# STM32F405.net
KiCad netlist of a schematic drawn in Altium Designer
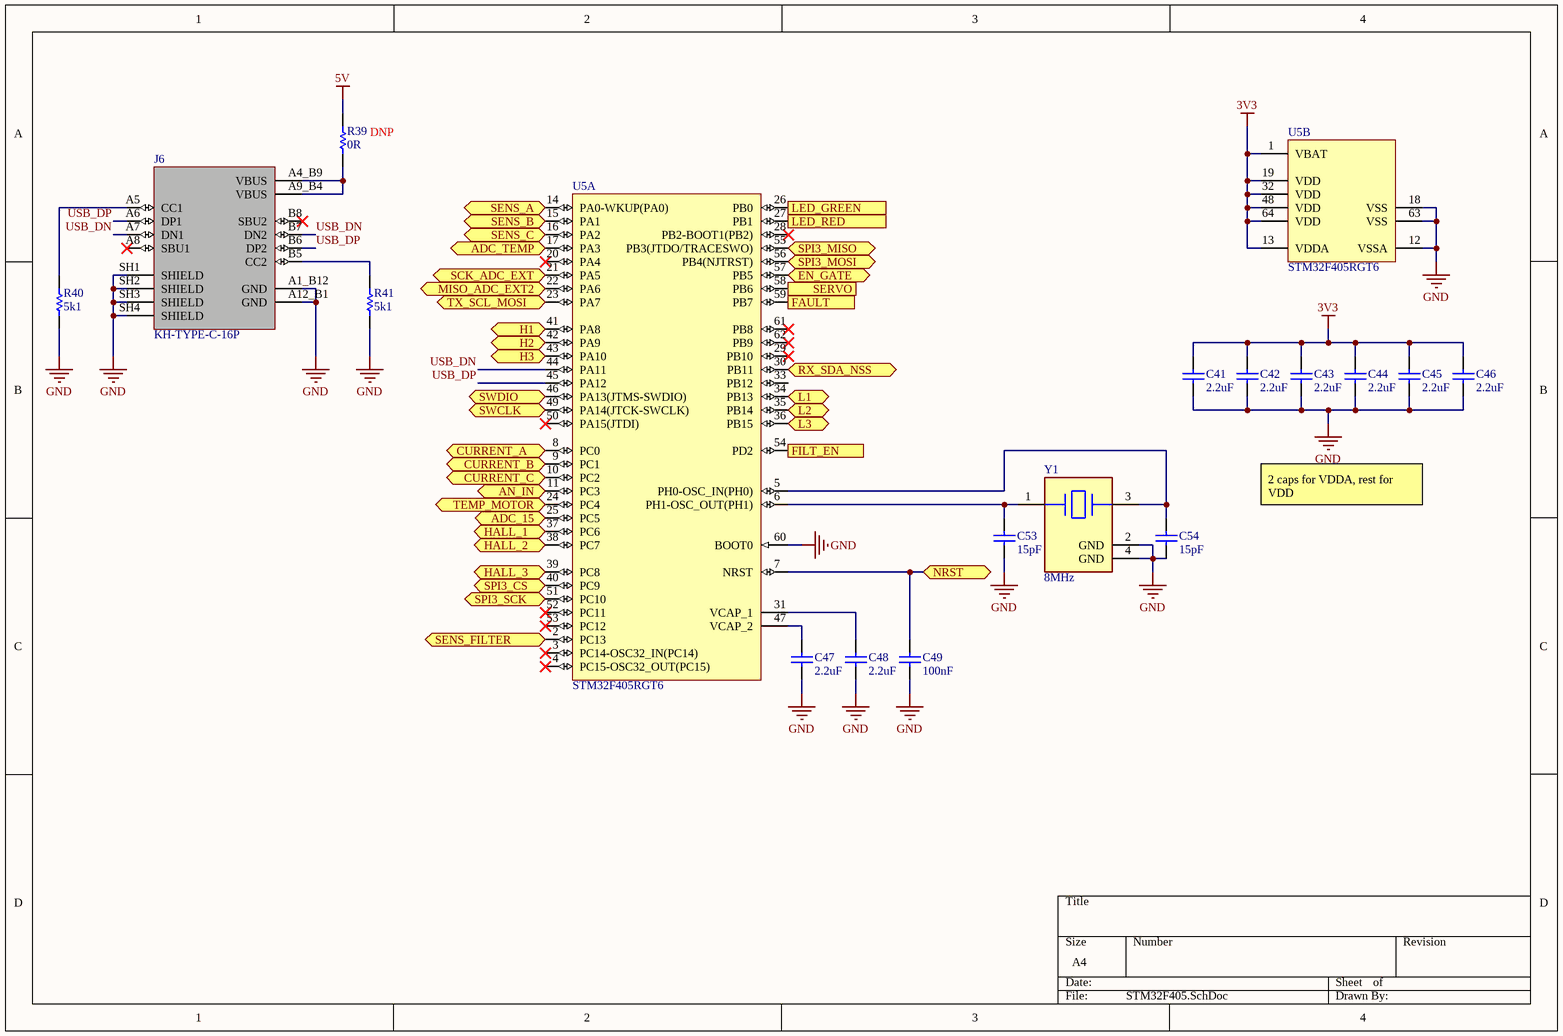
[diagram p0: STM32F405.SchDoc]

(export (version "E")
  (design (tool "Eeschema 10.0.6"))
  (components
    (comp (ref "C41")
      (value "2.2uF")
      (footprint "Wurth 0603 capacitor")
      (fields (field (name "Comment") "Generic Capacitor 2.2uF 0603"))
      (libsource (lib "Passives") (part "Generic Capacitor 2.2uF 0603"))
    )
    (comp (ref "C42")
      (value "2.2uF")
      (footprint "Wurth 0603 capacitor")
      (fields (field (name "Comment") "Generic Capacitor 2.2uF 0603"))
      (libsource (lib "Passives") (part "Generic Capacitor 2.2uF 0603"))
    )
    (comp (ref "C43")
      (value "2.2uF")
      (footprint "Wurth 0603 capacitor")
      (fields (field (name "Comment") "Generic Capacitor 2.2uF 0603"))
      (libsource (lib "Passives") (part "Generic Capacitor 2.2uF 0603"))
    )
    (comp (ref "C44")
      (value "2.2uF")
      (footprint "Wurth 0603 capacitor")
      (fields (field (name "Comment") "Generic Capacitor 2.2uF 0603"))
      (libsource (lib "Passives") (part "Generic Capacitor 2.2uF 0603"))
    )
    (comp (ref "C45")
      (value "2.2uF")
      (footprint "Wurth 0603 capacitor")
      (fields (field (name "Comment") "Generic Capacitor 2.2uF 0603"))
      (libsource (lib "Passives") (part "Generic Capacitor 2.2uF 0603"))
    )
    (comp (ref "C46")
      (value "2.2uF")
      (footprint "Wurth 0603 capacitor")
      (fields (field (name "Comment") "Generic Capacitor 2.2uF 0603"))
      (libsource (lib "Passives") (part "Generic Capacitor 2.2uF 0603"))
    )
    (comp (ref "C47")
      (value "2.2uF")
      (footprint "Wurth 0603 capacitor")
      (fields (field (name "Comment") "Generic Capacitor 2.2uF 0603"))
      (libsource (lib "Passives") (part "Generic Capacitor 2.2uF 0603"))
    )
    (comp (ref "C48")
      (value "2.2uF")
      (footprint "Wurth 0603 capacitor")
      (fields (field (name "Comment") "Generic Capacitor 2.2uF 0603"))
      (libsource (lib "Passives") (part "Generic Capacitor 2.2uF 0603"))
    )
    (comp (ref "C49")
      (value "100nF")
      (footprint "Wurth 0603 capacitor")
      (fields (field (name "Comment") "Generic Capacitor 100nF 0603"))
      (libsource (lib "Passives") (part "Generic Capacitor 100nF 0603"))
    )
    (comp (ref "C53")
      (value "15pF")
      (footprint "Wurth 0603 capacitor")
      (fields (field (name "Comment") "Generic Capacitor 15pF 0603"))
      (libsource (lib "Passives") (part "Generic Capacitor 15pF 0603"))
    )
    (comp (ref "C54")
      (value "15pF")
      (footprint "Wurth 0603 capacitor")
      (fields (field (name "Comment") "Generic Capacitor 15pF 0603"))
      (libsource (lib "Passives") (part "Generic Capacitor 15pF 0603"))
    )
    (comp (ref "J6")
      (value "KH-TYPE-C-16P")
      (footprint "KINGHELM_KH-TYPE-C-16P")
      (fields (field (name "MF") "kinghelm"))
      (libsource (lib "Connectors") (part "KH-TYPE-C-16P"))
    )
    (comp (ref "R39")
      (value "0R")
      (footprint "Wurth 0603 Resistor")
      (fields (field (name "Comment") "Generic Resistor 0R 0603"))
      (libsource (lib "Passives") (part "Generic Resistor 0R 0603"))
    )
    (comp (ref "R40")
      (value "5k1")
      (footprint "0805 Resistor")
      (fields (field (name "Comment") "Generic Resistor 5k1 0805"))
      (libsource (lib "Passives") (part "Generic Resistor 5k1 0805"))
    )
    (comp (ref "R41")
      (value "5k1")
      (footprint "0805 Resistor")
      (fields (field (name "Comment") "Generic Resistor 5k1 0805"))
      (libsource (lib "Passives") (part "Generic Resistor 5k1 0805"))
    )
    (comp (ref "U5")
      (value "STM32F405RGT6")
      (footprint "STM-LQFP64_M")
      (fields (field (name "MANUFACTURER") "STMicroelectronics"))
      (libsource (lib "Altium Content Vault") (part "MC-ARM-STM32F4X5-SQ64"))
    )
    (comp (ref "Y1")
      (value "8MHz")
      (footprint "huaxindianzi 8MHz Crystal")
      (fields (field (name "Comment") "CF4008M00012001"))
      (libsource (lib "Crystals") (part "8MHz huaxindianzi Crystal"))
    )
  )
  (nets
    (net (code "1") (name "/ADC_15") (class "Default")
      (node (ref "U5") (pin "25") (pinfunction "PC5_25") (pintype "bidirectional"))
    )
    (net (code "2") (name "/ADC_TEMP") (class "Default")
      (node (ref "U5") (pin "17") (pinfunction "PA3_17") (pintype "bidirectional"))
    )
    (net (code "3") (name "/AN_IN") (class "Default")
      (node (ref "U5") (pin "11") (pinfunction "PC3_11") (pintype "bidirectional"))
    )
    (net (code "4") (name "/CURRENT_A") (class "Default")
      (node (ref "U5") (pin "8") (pinfunction "PC0_8") (pintype "bidirectional"))
    )
    (net (code "5") (name "/CURRENT_B") (class "Default")
      (node (ref "U5") (pin "9") (pinfunction "PC1_9") (pintype "bidirectional"))
    )
    (net (code "6") (name "/CURRENT_C") (class "Default")
      (node (ref "U5") (pin "10") (pinfunction "PC2_10") (pintype "bidirectional"))
    )
    (net (code "7") (name "/EN_GATE") (class "Default")
      (node (ref "U5") (pin "57") (pinfunction "PB5_57") (pintype "bidirectional"))
    )
    (net (code "8") (name "/FAULT") (class "Default")
      (node (ref "U5") (pin "59") (pinfunction "PB7_59") (pintype "bidirectional"))
    )
    (net (code "9") (name "/FILT_EN") (class "Default")
      (node (ref "U5") (pin "54") (pinfunction "PD2_54") (pintype "bidirectional"))
    )
    (net (code "10") (name "/H1") (class "Default")
      (node (ref "U5") (pin "41") (pinfunction "PA8_41") (pintype "bidirectional"))
    )
    (net (code "11") (name "/H2") (class "Default")
      (node (ref "U5") (pin "42") (pinfunction "PA9_42") (pintype "bidirectional"))
    )
    (net (code "12") (name "/H3") (class "Default")
      (node (ref "U5") (pin "43") (pinfunction "PA10_43") (pintype "bidirectional"))
    )
    (net (code "13") (name "/HALL_1") (class "Default")
      (node (ref "U5") (pin "37") (pinfunction "PC6_37") (pintype "bidirectional"))
    )
    (net (code "14") (name "/HALL_2") (class "Default")
      (node (ref "U5") (pin "38") (pinfunction "PC7_38") (pintype "bidirectional"))
    )
    (net (code "15") (name "/HALL_3") (class "Default")
      (node (ref "U5") (pin "39") (pinfunction "PC8_39") (pintype "bidirectional"))
    )
    (net (code "16") (name "/L1") (class "Default")
      (node (ref "U5") (pin "34") (pinfunction "PB13_34") (pintype "bidirectional"))
    )
    (net (code "17") (name "/L2") (class "Default")
      (node (ref "U5") (pin "35") (pinfunction "PB14_35") (pintype "bidirectional"))
    )
    (net (code "18") (name "/L3") (class "Default")
      (node (ref "U5") (pin "36") (pinfunction "PB15_36") (pintype "bidirectional"))
    )
    (net (code "19") (name "/LED_GREEN") (class "Default")
      (node (ref "U5") (pin "26") (pinfunction "PB0_26") (pintype "bidirectional"))
    )
    (net (code "20") (name "/LED_RED") (class "Default")
      (node (ref "U5") (pin "27") (pinfunction "PB1_27") (pintype "bidirectional"))
    )
    (net (code "21") (name "/MISO_ADC_EXT2") (class "Default")
      (node (ref "U5") (pin "22") (pinfunction "PA6_22") (pintype "bidirectional"))
    )
    (net (code "22") (name "/NRST") (class "Default")
      (node (ref "C49") (pin "2") (pinfunction "2_2") (pintype "passive"))
      (node (ref "U5") (pin "7") (pinfunction "NRST_7") (pintype "bidirectional"))
    )
    (net (code "23") (name "/RX_SDA_NSS") (class "Default")
      (node (ref "U5") (pin "30") (pinfunction "PB11_30") (pintype "bidirectional"))
    )
    (net (code "24") (name "/SCK_ADC_EXT") (class "Default")
      (node (ref "U5") (pin "21") (pinfunction "PA5_21") (pintype "bidirectional"))
    )
    (net (code "25") (name "/SENS_A") (class "Default")
      (node (ref "U5") (pin "14") (pinfunction "PA0-WKUP(PA0)_14") (pintype "bidirectional"))
    )
    (net (code "26") (name "/SENS_B") (class "Default")
      (node (ref "U5") (pin "15") (pinfunction "PA1_15") (pintype "bidirectional"))
    )
    (net (code "27") (name "/SENS_C") (class "Default")
      (node (ref "U5") (pin "16") (pinfunction "PA2_16") (pintype "bidirectional"))
    )
    (net (code "28") (name "/SENS_FILTER") (class "Default")
      (node (ref "U5") (pin "2") (pinfunction "PC13_2") (pintype "bidirectional"))
    )
    (net (code "29") (name "/SERVO") (class "Default")
      (node (ref "U5") (pin "58") (pinfunction "PB6_58") (pintype "bidirectional"))
    )
    (net (code "30") (name "/SPI3_CS") (class "Default")
      (node (ref "U5") (pin "40") (pinfunction "PC9_40") (pintype "bidirectional"))
    )
    (net (code "31") (name "/SPI3_MISO") (class "Default")
      (node (ref "U5") (pin "55") (pinfunction "PB3(JTDO/TRACESWO)_55") (pintype "bidirectional"))
    )
    (net (code "32") (name "/SPI3_MOSI") (class "Default")
      (node (ref "U5") (pin "56") (pinfunction "PB4(NJTRST)_56") (pintype "bidirectional"))
    )
    (net (code "33") (name "/SPI3_SCK") (class "Default")
      (node (ref "U5") (pin "51") (pinfunction "PC10_51") (pintype "bidirectional"))
    )
    (net (code "34") (name "/SWCLK") (class "Default")
      (node (ref "U5") (pin "49") (pinfunction "PA14(JTCK-SWCLK)_49") (pintype "bidirectional"))
    )
    (net (code "35") (name "/SWDIO") (class "Default")
      (node (ref "U5") (pin "46") (pinfunction "PA13(JTMS-SWDIO)_46") (pintype "bidirectional"))
    )
    (net (code "36") (name "/TEMP_MOTOR") (class "Default")
      (node (ref "U5") (pin "24") (pinfunction "PC4_24") (pintype "bidirectional"))
    )
    (net (code "37") (name "/TX_SCL_MOSI") (class "Default")
      (node (ref "U5") (pin "23") (pinfunction "PA7_23") (pintype "bidirectional"))
    )
    (net (code "38") (name "/USB_DN") (class "Default")
      (node (ref "J6") (pin "A7") (pinfunction "DN1_A7") (pintype "bidirectional"))
      (node (ref "J6") (pin "B7") (pinfunction "DN2_B7") (pintype "bidirectional"))
      (node (ref "U5") (pin "44") (pinfunction "PA11_44") (pintype "bidirectional"))
    )
    (net (code "39") (name "/USB_DP") (class "Default")
      (node (ref "J6") (pin "A6") (pinfunction "DP1_A6") (pintype "bidirectional"))
      (node (ref "J6") (pin "B6") (pinfunction "DP2_B6") (pintype "bidirectional"))
      (node (ref "U5") (pin "45") (pinfunction "PA12_45") (pintype "bidirectional"))
    )
    (net (code "40") (name "3V3") (class "Default")
      (node (ref "C41") (pin "2") (pinfunction "2_2") (pintype "passive"))
      (node (ref "C42") (pin "2") (pinfunction "2_2") (pintype "passive"))
      (node (ref "C43") (pin "2") (pinfunction "2_2") (pintype "passive"))
      (node (ref "C44") (pin "2") (pinfunction "2_2") (pintype "passive"))
      (node (ref "C45") (pin "2") (pinfunction "2_2") (pintype "passive"))
      (node (ref "C46") (pin "2") (pinfunction "2_2") (pintype "passive"))
      (node (ref "U5") (pin "1") (pinfunction "VBAT_1") (pintype "power_in"))
      (node (ref "U5") (pin "13") (pinfunction "VDDA_13") (pintype "power_in"))
      (node (ref "U5") (pin "19") (pinfunction "VDD_19") (pintype "power_in"))
      (node (ref "U5") (pin "32") (pinfunction "VDD_32") (pintype "power_in"))
      (node (ref "U5") (pin "48") (pinfunction "VDD_48") (pintype "power_in"))
      (node (ref "U5") (pin "64") (pinfunction "VDD_64") (pintype "power_in"))
    )
    (net (code "41") (name "5V") (class "Default")
      (node (ref "R39") (pin "2") (pinfunction "2_2") (pintype "passive"))
    )
    (net (code "42") (name "GND") (class "Default")
      (node (ref "C41") (pin "1") (pinfunction "1_1") (pintype "passive"))
      (node (ref "C42") (pin "1") (pinfunction "1_1") (pintype "passive"))
      (node (ref "C43") (pin "1") (pinfunction "1_1") (pintype "passive"))
      (node (ref "C44") (pin "1") (pinfunction "1_1") (pintype "passive"))
      (node (ref "C45") (pin "1") (pinfunction "1_1") (pintype "passive"))
      (node (ref "C46") (pin "1") (pinfunction "1_1") (pintype "passive"))
      (node (ref "C47") (pin "1") (pinfunction "1_1") (pintype "passive"))
      (node (ref "C48") (pin "1") (pinfunction "1_1") (pintype "passive"))
      (node (ref "C49") (pin "1") (pinfunction "1_1") (pintype "passive"))
      (node (ref "C53") (pin "1") (pinfunction "1_1") (pintype "passive"))
      (node (ref "C54") (pin "1") (pinfunction "1_1") (pintype "passive"))
      (node (ref "J6") (pin "A12_B1") (pinfunction "GND_A12_B1") (pintype "power_in"))
      (node (ref "J6") (pin "A1_B12") (pinfunction "GND_A1_B12") (pintype "power_in"))
      (node (ref "J6") (pin "SH1") (pinfunction "SHIELD_SH1") (pintype "passive"))
      (node (ref "J6") (pin "SH2") (pinfunction "SHIELD_SH2") (pintype "passive"))
      (node (ref "J6") (pin "SH3") (pinfunction "SHIELD_SH3") (pintype "passive"))
      (node (ref "J6") (pin "SH4") (pinfunction "SHIELD_SH4") (pintype "passive"))
      (node (ref "R40") (pin "1") (pinfunction "1_1") (pintype "passive"))
      (node (ref "R41") (pin "1") (pinfunction "1_1") (pintype "passive"))
      (node (ref "U5") (pin "12") (pinfunction "VSSA_12") (pintype "power_in"))
      (node (ref "U5") (pin "18") (pinfunction "VSS_18") (pintype "power_in"))
      (node (ref "U5") (pin "60") (pinfunction "BOOT0_60") (pintype "input"))
      (node (ref "U5") (pin "63") (pinfunction "VSS_63") (pintype "power_in"))
      (node (ref "Y1") (pin "2") (pinfunction "GND_2") (pintype "power_in"))
      (node (ref "Y1") (pin "4") (pinfunction "GND_4") (pintype "power_in"))
    )
    (net (code "43") (name "Net-(J6-CC1)") (class "Default")
      (node (ref "J6") (pin "A5") (pinfunction "CC1_A5") (pintype "bidirectional"))
      (node (ref "R40") (pin "2") (pinfunction "2_2") (pintype "passive"))
    )
    (net (code "44") (name "Net-(J6-CC2)") (class "Default")
      (node (ref "J6") (pin "B5") (pinfunction "CC2_B5") (pintype "bidirectional"))
      (node (ref "R41") (pin "2") (pinfunction "2_2") (pintype "passive"))
    )
    (net (code "45") (name "Net-(J6-VBUS-PadA4_B9)") (class "Default")
      (node (ref "J6") (pin "A4_B9") (pinfunction "VBUS_A4_B9") (pintype "power_in"))
      (node (ref "J6") (pin "A9_B4") (pinfunction "VBUS_A9_B4") (pintype "power_in"))
      (node (ref "R39") (pin "1") (pinfunction "1_1") (pintype "passive"))
    )
    (net (code "46") (name "Net-(U5A-PH0-OSC_IN(PH0))") (class "Default")
      (node (ref "C54") (pin "2") (pinfunction "2_2") (pintype "passive"))
      (node (ref "U5") (pin "5") (pinfunction "PH0-OSC_IN(PH0)_5") (pintype "bidirectional"))
      (node (ref "Y1") (pin "3") (pinfunction "3_3") (pintype "passive"))
    )
    (net (code "47") (name "Net-(U5A-PH1-OSC_OUT(PH1))") (class "Default")
      (node (ref "C53") (pin "2") (pinfunction "2_2") (pintype "passive"))
      (node (ref "U5") (pin "6") (pinfunction "PH1-OSC_OUT(PH1)_6") (pintype "bidirectional"))
      (node (ref "Y1") (pin "1") (pinfunction "1_1") (pintype "passive"))
    )
    (net (code "48") (name "Net-(U5A-VCAP_1)") (class "Default")
      (node (ref "C48") (pin "2") (pinfunction "2_2") (pintype "passive"))
      (node (ref "U5") (pin "31") (pinfunction "VCAP_1_31") (pintype "power_in"))
    )
    (net (code "49") (name "Net-(U5A-VCAP_2)") (class "Default")
      (node (ref "C47") (pin "2") (pinfunction "2_2") (pintype "passive"))
      (node (ref "U5") (pin "47") (pinfunction "VCAP_2_47") (pintype "power_in"))
    )
    (net (code "50") (name "unconnected-(J6-SBU1-PadA8)") (class "Default")
      (node (ref "J6") (pin "A8") (pinfunction "SBU1_A8") (pintype "bidirectional+no_connect"))
    )
    (net (code "51") (name "unconnected-(J6-SBU2-PadB8)") (class "Default")
      (node (ref "J6") (pin "B8") (pinfunction "SBU2_B8") (pintype "bidirectional+no_connect"))
    )
    (net (code "52") (name "unconnected-(U5A-PA4-Pad20)") (class "Default")
      (node (ref "U5") (pin "20") (pinfunction "PA4_20") (pintype "bidirectional+no_connect"))
    )
    (net (code "53") (name "unconnected-(U5A-PA15(JTDI)-Pad50)") (class "Default")
      (node (ref "U5") (pin "50") (pinfunction "PA15(JTDI)_50") (pintype "bidirectional+no_connect"))
    )
    (net (code "54") (name "unconnected-(U5A-PB2-BOOT1(PB2)-Pad28)") (class "Default")
      (node (ref "U5") (pin "28") (pinfunction "PB2-BOOT1(PB2)_28") (pintype "bidirectional+no_connect"))
    )
    (net (code "55") (name "unconnected-(U5A-PB8-Pad61)") (class "Default")
      (node (ref "U5") (pin "61") (pinfunction "PB8_61") (pintype "bidirectional+no_connect"))
    )
    (net (code "56") (name "unconnected-(U5A-PB9-Pad62)") (class "Default")
      (node (ref "U5") (pin "62") (pinfunction "PB9_62") (pintype "bidirectional+no_connect"))
    )
    (net (code "57") (name "unconnected-(U5A-PB10-Pad29)") (class "Default")
      (node (ref "U5") (pin "29") (pinfunction "PB10_29") (pintype "bidirectional+no_connect"))
    )
    (net (code "58") (name "unconnected-(U5A-PB12-Pad33)") (class "Default")
      (node (ref "U5") (pin "33") (pinfunction "PB12_33") (pintype "bidirectional"))
    )
    (net (code "59") (name "unconnected-(U5A-PC11-Pad52)") (class "Default")
      (node (ref "U5") (pin "52") (pinfunction "PC11_52") (pintype "bidirectional+no_connect"))
    )
    (net (code "60") (name "unconnected-(U5A-PC12-Pad53)") (class "Default")
      (node (ref "U5") (pin "53") (pinfunction "PC12_53") (pintype "bidirectional+no_connect"))
    )
    (net (code "61") (name "unconnected-(U5A-PC14-OSC32_IN(PC14)-Pad3)") (class "Default")
      (node (ref "U5") (pin "3") (pinfunction "PC14-OSC32_IN(PC14)_3") (pintype "bidirectional+no_connect"))
    )
    (net (code "62") (name "unconnected-(U5A-PC15-OSC32_OUT(PC15)-Pad4)") (class "Default")
      (node (ref "U5") (pin "4") (pinfunction "PC15-OSC32_OUT(PC15)_4") (pintype "bidirectional+no_connect"))
    )
  )
)
